# stepper-v1_1.net
KiCad netlist of a schematic drawn in EAGLE
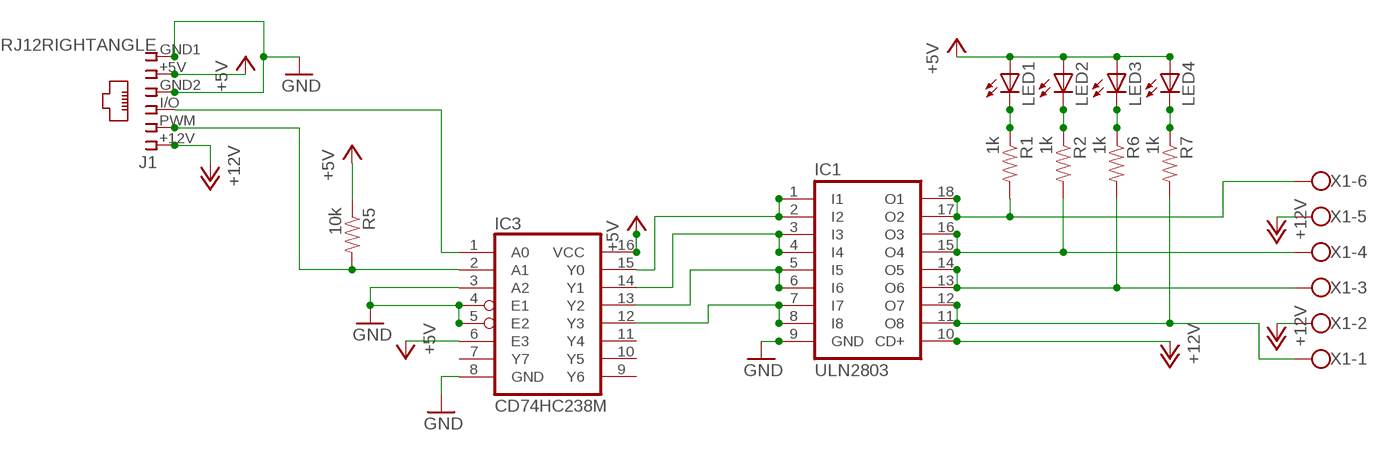
[diagram p0: schematic, sheet 1]

(export (version "E")
  (design (tool "Eeschema 10.0.6"))
  (components
    (comp (ref "IC1")
      (value "ULN2803")
      (footprint "eagle-import:SO18W")
      (libsource (lib "eagle-import") (part "ULN2803A"))
    )
    (comp (ref "IC3")
      (value "CD74HC238M")
      (footprint "eagle-import:SO16")
      (libsource (lib "eagle-import") (part "74238D"))
    )
    (comp (ref "J1")
      (value "RJ12RIGHTANGLE")
      (footprint "eagle-import:RJ12-RIGHTANGLE")
      (libsource (lib "eagle-import") (part "RJ12RIGHTANGLE"))
    )
    (comp (ref "LED1")
      (value "LED3MM")
      (footprint "eagle-import:LED3MM")
      (libsource (lib "eagle-import") (part "LED3MM"))
    )
    (comp (ref "LED2")
      (value "LED3MM")
      (footprint "eagle-import:LED3MM")
      (libsource (lib "eagle-import") (part "LED3MM"))
    )
    (comp (ref "LED3")
      (value "LED3MM")
      (footprint "eagle-import:LED3MM")
      (libsource (lib "eagle-import") (part "LED3MM"))
    )
    (comp (ref "LED4")
      (value "LED3MM")
      (footprint "eagle-import:LED3MM")
      (libsource (lib "eagle-import") (part "LED3MM"))
    )
    (comp (ref "R1")
      (value "1k")
      (footprint "eagle-import:1206")
      (libsource (lib "eagle-import") (part "RESISTOR1206"))
    )
    (comp (ref "R2")
      (value "1k")
      (footprint "eagle-import:1206")
      (libsource (lib "eagle-import") (part "RESISTOR1206"))
    )
    (comp (ref "R5")
      (value "10k")
      (footprint "eagle-import:1206")
      (libsource (lib "eagle-import") (part "RESISTOR1206"))
    )
    (comp (ref "R6")
      (value "1k")
      (footprint "eagle-import:1206")
      (libsource (lib "eagle-import") (part "RESISTOR1206"))
    )
    (comp (ref "R7")
      (value "1k")
      (footprint "eagle-import:1206")
      (libsource (lib "eagle-import") (part "RESISTOR1206"))
    )
    (comp (ref "X1")
      (value "W237-6")
      (footprint "eagle-import:W237-6")
      (libsource (lib "eagle-import") (part "W237-6"))
    )
  )
  (nets
    (net (code "1") (name "+5V") (class "Default")
      (node (ref "IC3") (pin "16") (pinfunction "VCC_16") (pintype "power_in"))
      (node (ref "IC3") (pin "6") (pinfunction "E3_6") (pintype "input"))
      (node (ref "J1") (pin "+5V") (pinfunction "5_+5V") (pintype "bidirectional"))
      (node (ref "LED1") (pin "A") (pinfunction "A_A") (pintype "passive"))
      (node (ref "LED2") (pin "A") (pinfunction "A_A") (pintype "passive"))
      (node (ref "LED3") (pin "A") (pinfunction "A_A") (pintype "passive"))
      (node (ref "LED4") (pin "A") (pinfunction "A_A") (pintype "passive"))
      (node (ref "R5") (pin "1") (pinfunction "1_1") (pintype "passive"))
    )
    (net (code "2") (name "+12V") (class "Default")
      (node (ref "IC1") (pin "10") (pinfunction "CD+_10") (pintype "passive"))
      (node (ref "J1") (pin "+12V") (pinfunction "1_+12V") (pintype "bidirectional"))
      (node (ref "X1") (pin "2") (pinfunction "KL_2") (pintype "passive"))
      (node (ref "X1") (pin "5") (pinfunction "KL_5") (pintype "passive"))
    )
    (net (code "3") (name "GND") (class "Default")
      (node (ref "IC1") (pin "9") (pinfunction "GND_9") (pintype "power_in"))
      (node (ref "IC3") (pin "3") (pinfunction "A2_3") (pintype "input"))
      (node (ref "IC3") (pin "4") (pinfunction "E1_4") (pintype "input"))
      (node (ref "IC3") (pin "5") (pinfunction "E2_5") (pintype "input"))
      (node (ref "IC3") (pin "8") (pinfunction "GND_8") (pintype "power_in"))
      (node (ref "J1") (pin "GND1") (pinfunction "6_GND1") (pintype "bidirectional"))
      (node (ref "J1") (pin "GND2") (pinfunction "4_GND2") (pintype "bidirectional"))
    )
    (net (code "4") (name "Net-(IC1-I1)") (class "Default")
      (node (ref "IC1") (pin "1") (pinfunction "I1_1") (pintype "input"))
      (node (ref "IC1") (pin "2") (pinfunction "I2_2") (pintype "input"))
      (node (ref "IC3") (pin "15") (pinfunction "Y0_15") (pintype "output"))
    )
    (net (code "5") (name "Net-(IC1-I3)") (class "Default")
      (node (ref "IC1") (pin "3") (pinfunction "I3_3") (pintype "input"))
      (node (ref "IC1") (pin "4") (pinfunction "I4_4") (pintype "input"))
      (node (ref "IC3") (pin "14") (pinfunction "Y1_14") (pintype "output"))
    )
    (net (code "6") (name "Net-(IC1-I5)") (class "Default")
      (node (ref "IC1") (pin "5") (pinfunction "I5_5") (pintype "input"))
      (node (ref "IC1") (pin "6") (pinfunction "I6_6") (pintype "input"))
      (node (ref "IC3") (pin "13") (pinfunction "Y2_13") (pintype "output"))
    )
    (net (code "7") (name "Net-(IC1-I7)") (class "Default")
      (node (ref "IC1") (pin "7") (pinfunction "I7_7") (pintype "input"))
      (node (ref "IC1") (pin "8") (pinfunction "I8_8") (pintype "input"))
      (node (ref "IC3") (pin "12") (pinfunction "Y3_12") (pintype "output"))
    )
    (net (code "8") (name "Net-(IC1-O1)") (class "Default")
      (node (ref "IC1") (pin "17") (pinfunction "O2_17") (pintype "open_collector"))
      (node (ref "IC1") (pin "18") (pinfunction "O1_18") (pintype "open_collector"))
      (node (ref "R1") (pin "2") (pinfunction "2_2") (pintype "passive"))
      (node (ref "X1") (pin "6") (pinfunction "KL_6") (pintype "passive"))
    )
    (net (code "9") (name "Net-(IC1-O3)") (class "Default")
      (node (ref "IC1") (pin "15") (pinfunction "O4_15") (pintype "open_collector"))
      (node (ref "IC1") (pin "16") (pinfunction "O3_16") (pintype "open_collector"))
      (node (ref "R2") (pin "2") (pinfunction "2_2") (pintype "passive"))
      (node (ref "X1") (pin "4") (pinfunction "KL_4") (pintype "passive"))
    )
    (net (code "10") (name "Net-(IC1-O5)") (class "Default")
      (node (ref "IC1") (pin "13") (pinfunction "O6_13") (pintype "open_collector"))
      (node (ref "IC1") (pin "14") (pinfunction "O5_14") (pintype "open_collector"))
      (node (ref "R6") (pin "2") (pinfunction "2_2") (pintype "passive"))
      (node (ref "X1") (pin "3") (pinfunction "KL_3") (pintype "passive"))
    )
    (net (code "11") (name "Net-(IC1-O7)") (class "Default")
      (node (ref "IC1") (pin "11") (pinfunction "O8_11") (pintype "open_collector"))
      (node (ref "IC1") (pin "12") (pinfunction "O7_12") (pintype "open_collector"))
      (node (ref "R7") (pin "2") (pinfunction "2_2") (pintype "passive"))
      (node (ref "X1") (pin "1") (pinfunction "KL_1") (pintype "passive"))
    )
    (net (code "12") (name "Net-(IC3-A0)") (class "Default")
      (node (ref "IC3") (pin "1") (pinfunction "A0_1") (pintype "input"))
      (node (ref "J1") (pin "I/O") (pinfunction "3_I/O") (pintype "bidirectional"))
    )
    (net (code "13") (name "Net-(IC3-A1)") (class "Default")
      (node (ref "IC3") (pin "2") (pinfunction "A1_2") (pintype "input"))
      (node (ref "J1") (pin "PWM") (pinfunction "2_PWM") (pintype "bidirectional"))
      (node (ref "R5") (pin "2") (pinfunction "2_2") (pintype "passive"))
    )
    (net (code "14") (name "Net-(LED1-C)") (class "Default")
      (node (ref "LED1") (pin "K") (pinfunction "C_K") (pintype "passive"))
      (node (ref "R1") (pin "1") (pinfunction "1_1") (pintype "passive"))
    )
    (net (code "15") (name "Net-(LED2-C)") (class "Default")
      (node (ref "LED2") (pin "K") (pinfunction "C_K") (pintype "passive"))
      (node (ref "R2") (pin "1") (pinfunction "1_1") (pintype "passive"))
    )
    (net (code "16") (name "Net-(LED3-C)") (class "Default")
      (node (ref "LED3") (pin "K") (pinfunction "C_K") (pintype "passive"))
      (node (ref "R6") (pin "1") (pinfunction "1_1") (pintype "passive"))
    )
    (net (code "17") (name "Net-(LED4-C)") (class "Default")
      (node (ref "LED4") (pin "K") (pinfunction "C_K") (pintype "passive"))
      (node (ref "R7") (pin "1") (pinfunction "1_1") (pintype "passive"))
    )
    (net (code "18") (name "unconnected-(IC3-Y4-Pad11)") (class "Default")
      (node (ref "IC3") (pin "11") (pinfunction "Y4_11") (pintype "output"))
    )
    (net (code "19") (name "unconnected-(IC3-Y5-Pad10)") (class "Default")
      (node (ref "IC3") (pin "10") (pinfunction "Y5_10") (pintype "output"))
    )
    (net (code "20") (name "unconnected-(IC3-Y6-Pad9)") (class "Default")
      (node (ref "IC3") (pin "9") (pinfunction "Y6_9") (pintype "output"))
    )
    (net (code "21") (name "unconnected-(IC3-Y7-Pad7)") (class "Default")
      (node (ref "IC3") (pin "7") (pinfunction "Y7_7") (pintype "output"))
    )
  )
)
